# 1.net
KiCad netlist of a schematic drawn in EAGLE
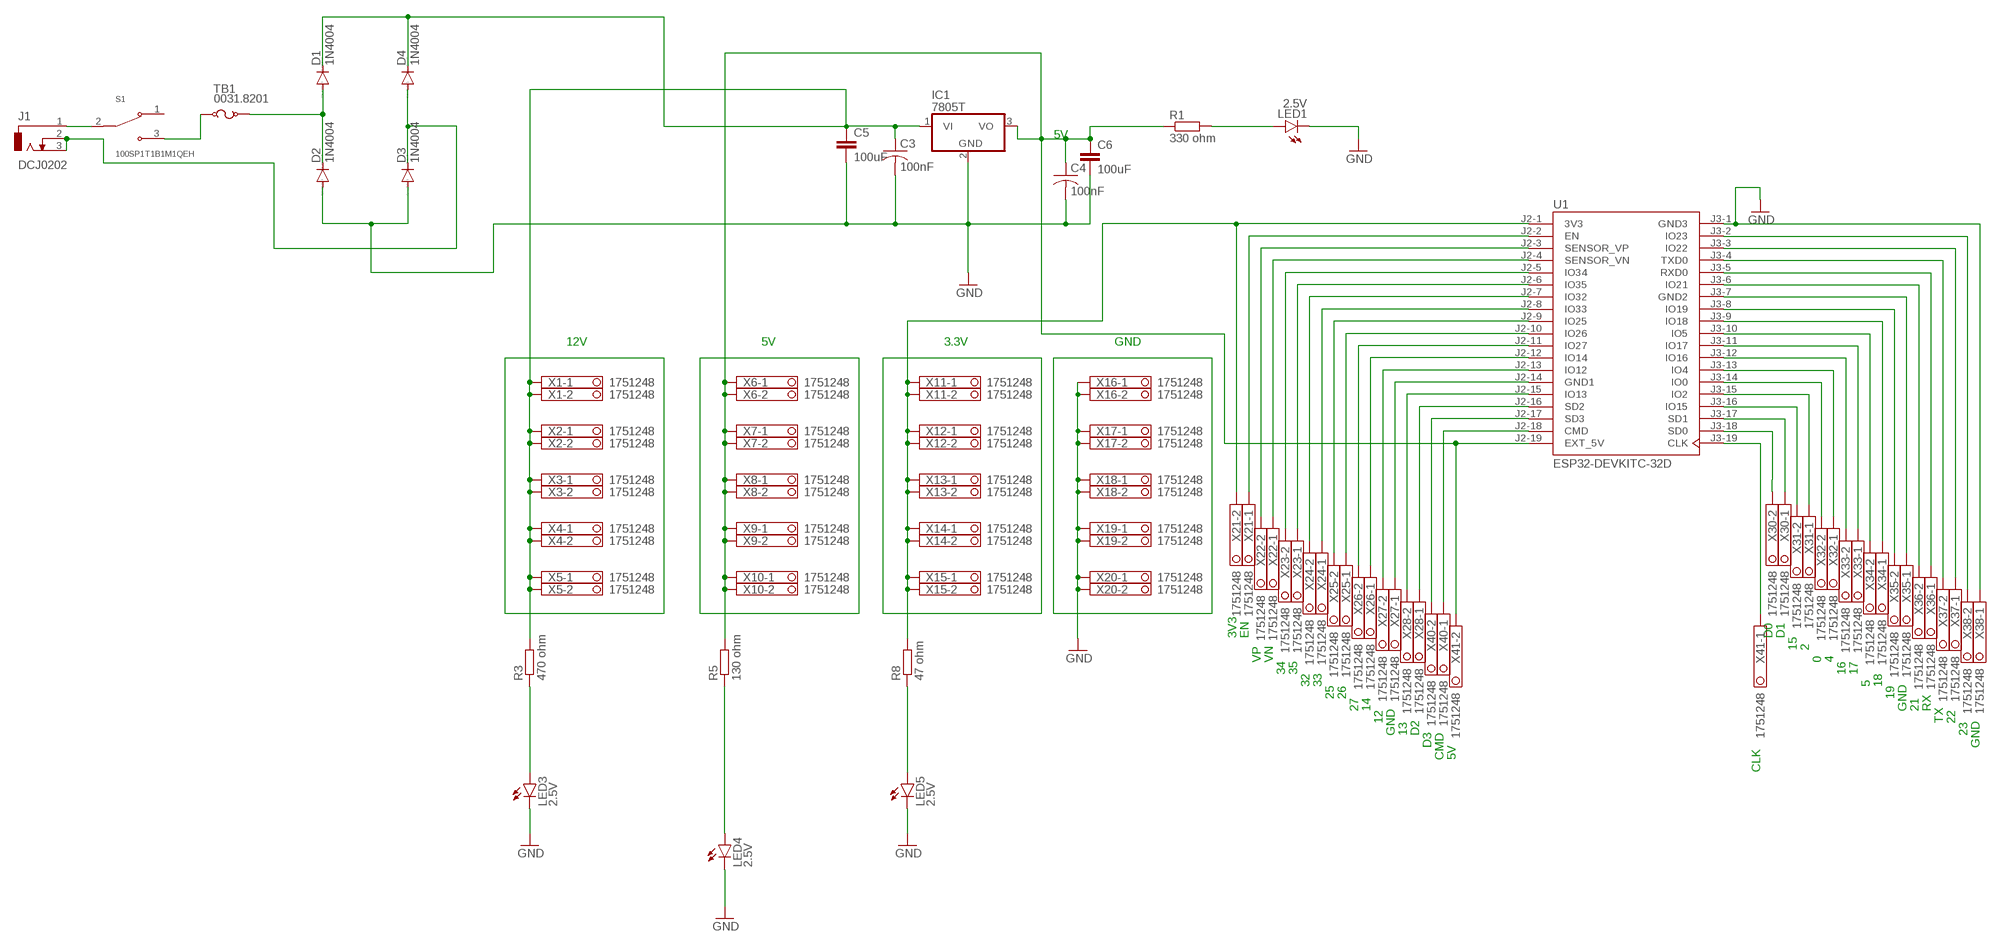
[diagram p0: schematic, sheet 1]

(export (version "E")
  (design (tool "Eeschema 10.0.6"))
  (components
    (comp (ref "C3")
      (value "100nF")
      (footprint "eagle-import:C025-024X044")
      (libsource (lib "eagle-import") (part "C-US025-024X044"))
    )
    (comp (ref "C4")
      (value "100nF")
      (footprint "eagle-import:C025-024X044")
      (libsource (lib "eagle-import") (part "C-US025-024X044"))
    )
    (comp (ref "C5")
      (value "100uF")
      (footprint "eagle-import:C025-050X050")
      (libsource (lib "eagle-import") (part "C-EU025-050X050"))
    )
    (comp (ref "C6")
      (value "100uF")
      (footprint "eagle-import:C025-050X050")
      (libsource (lib "eagle-import") (part "C-EU025-050X050"))
    )
    (comp (ref "D1")
      (value "1N4004")
      (footprint "eagle-import:DO41-10")
      (libsource (lib "eagle-import") (part "1N4004"))
    )
    (comp (ref "D2")
      (value "1N4004")
      (footprint "eagle-import:DO41-10")
      (libsource (lib "eagle-import") (part "1N4004"))
    )
    (comp (ref "D3")
      (value "1N4004")
      (footprint "eagle-import:DO41-10")
      (libsource (lib "eagle-import") (part "1N4004"))
    )
    (comp (ref "D4")
      (value "1N4004")
      (footprint "eagle-import:DO41-10")
      (libsource (lib "eagle-import") (part "1N4004"))
    )
    (comp (ref "IC1")
      (value "7805T")
      (footprint "eagle-import:TO220H")
      (libsource (lib "eagle-import") (part "78T05"))
    )
    (comp (ref "J1")
      (value "DCJ0202")
      (footprint "eagle-import:DCJ0202")
      (libsource (lib "eagle-import") (part "DCJ0202"))
    )
    (comp (ref "LED1")
      (value "2.5V")
      (footprint "eagle-import:LED3MM")
      (libsource (lib "eagle-import") (part "LED3MM"))
    )
    (comp (ref "LED3")
      (value "2.5V")
      (footprint "eagle-import:LED3MM")
      (libsource (lib "eagle-import") (part "LED3MM"))
    )
    (comp (ref "LED4")
      (value "2.5V")
      (footprint "eagle-import:LED3MM")
      (libsource (lib "eagle-import") (part "LED3MM"))
    )
    (comp (ref "LED5")
      (value "2.5V")
      (footprint "eagle-import:LED3MM")
      (libsource (lib "eagle-import") (part "LED3MM"))
    )
    (comp (ref "R1")
      (value "330 ohm")
      (footprint "eagle-import:0207_10")
      (libsource (lib "eagle-import") (part "R-EU_0207/10"))
    )
    (comp (ref "R3")
      (value "470 ohm")
      (footprint "eagle-import:0207_10")
      (libsource (lib "eagle-import") (part "R-EU_0207/10"))
    )
    (comp (ref "R5")
      (value "130 ohm")
      (footprint "eagle-import:0207_10")
      (libsource (lib "eagle-import") (part "R-EU_0207/10"))
    )
    (comp (ref "R8")
      (value "47 ohm")
      (footprint "eagle-import:0207_10")
      (libsource (lib "eagle-import") (part "R-EU_0207/10"))
    )
    (comp (ref "S1")
      (value "100SP1T1B1M1QEH")
      (footprint "eagle-import:SW_100SP1T1B1M1QEH")
      (fields (field (name "MF") "E-Switch"))
      (libsource (lib "eagle-import") (part "100SP1T1B1M1QEH"))
    )
    (comp (ref "TB1")
      (value "0031.8201")
      (footprint "eagle-import:SCHURTER_0031.8201")
      (fields (field (name "MF") "Schurter Inc."))
      (libsource (lib "eagle-import") (part "0031.8201"))
    )
    (comp (ref "U1")
      (value "ESP32-DEVKITC-32D")
      (footprint "eagle-import:MODULE_ESP32-DEVKITC-32D")
      (fields (field (name "MF") "Espressif Systems"))
      (libsource (lib "eagle-import") (part "ESP32-DEVKITC-32D"))
    )
    (comp (ref "X1")
      (value "1751248")
      (footprint "eagle-import:1751248")
      (libsource (lib "eagle-import") (part "1751248"))
    )
    (comp (ref "X2")
      (value "1751248")
      (footprint "eagle-import:1751248")
      (libsource (lib "eagle-import") (part "1751248"))
    )
    (comp (ref "X3")
      (value "1751248")
      (footprint "eagle-import:1751248")
      (libsource (lib "eagle-import") (part "1751248"))
    )
    (comp (ref "X4")
      (value "1751248")
      (footprint "eagle-import:1751248")
      (libsource (lib "eagle-import") (part "1751248"))
    )
    (comp (ref "X5")
      (value "1751248")
      (footprint "eagle-import:1751248")
      (libsource (lib "eagle-import") (part "1751248"))
    )
    (comp (ref "X6")
      (value "1751248")
      (footprint "eagle-import:1751248")
      (libsource (lib "eagle-import") (part "1751248"))
    )
    (comp (ref "X7")
      (value "1751248")
      (footprint "eagle-import:1751248")
      (libsource (lib "eagle-import") (part "1751248"))
    )
    (comp (ref "X8")
      (value "1751248")
      (footprint "eagle-import:1751248")
      (libsource (lib "eagle-import") (part "1751248"))
    )
    (comp (ref "X9")
      (value "1751248")
      (footprint "eagle-import:1751248")
      (libsource (lib "eagle-import") (part "1751248"))
    )
    (comp (ref "X10")
      (value "1751248")
      (footprint "eagle-import:1751248")
      (libsource (lib "eagle-import") (part "1751248"))
    )
    (comp (ref "X11")
      (value "1751248")
      (footprint "eagle-import:1751248")
      (libsource (lib "eagle-import") (part "1751248"))
    )
    (comp (ref "X12")
      (value "1751248")
      (footprint "eagle-import:1751248")
      (libsource (lib "eagle-import") (part "1751248"))
    )
    (comp (ref "X13")
      (value "1751248")
      (footprint "eagle-import:1751248")
      (libsource (lib "eagle-import") (part "1751248"))
    )
    (comp (ref "X14")
      (value "1751248")
      (footprint "eagle-import:1751248")
      (libsource (lib "eagle-import") (part "1751248"))
    )
    (comp (ref "X15")
      (value "1751248")
      (footprint "eagle-import:1751248")
      (libsource (lib "eagle-import") (part "1751248"))
    )
    (comp (ref "X16")
      (value "1751248")
      (footprint "eagle-import:1751248")
      (libsource (lib "eagle-import") (part "1751248"))
    )
    (comp (ref "X17")
      (value "1751248")
      (footprint "eagle-import:1751248")
      (libsource (lib "eagle-import") (part "1751248"))
    )
    (comp (ref "X18")
      (value "1751248")
      (footprint "eagle-import:1751248")
      (libsource (lib "eagle-import") (part "1751248"))
    )
    (comp (ref "X19")
      (value "1751248")
      (footprint "eagle-import:1751248")
      (libsource (lib "eagle-import") (part "1751248"))
    )
    (comp (ref "X20")
      (value "1751248")
      (footprint "eagle-import:1751248")
      (libsource (lib "eagle-import") (part "1751248"))
    )
    (comp (ref "X21")
      (value "1751248")
      (footprint "eagle-import:1751248")
      (libsource (lib "eagle-import") (part "1751248"))
    )
    (comp (ref "X22")
      (value "1751248")
      (footprint "eagle-import:1751248")
      (libsource (lib "eagle-import") (part "1751248"))
    )
    (comp (ref "X23")
      (value "1751248")
      (footprint "eagle-import:1751248")
      (libsource (lib "eagle-import") (part "1751248"))
    )
    (comp (ref "X24")
      (value "1751248")
      (footprint "eagle-import:1751248")
      (libsource (lib "eagle-import") (part "1751248"))
    )
    (comp (ref "X25")
      (value "1751248")
      (footprint "eagle-import:1751248")
      (libsource (lib "eagle-import") (part "1751248"))
    )
    (comp (ref "X26")
      (value "1751248")
      (footprint "eagle-import:1751248")
      (libsource (lib "eagle-import") (part "1751248"))
    )
    (comp (ref "X27")
      (value "1751248")
      (footprint "eagle-import:1751248")
      (libsource (lib "eagle-import") (part "1751248"))
    )
    (comp (ref "X28")
      (value "1751248")
      (footprint "eagle-import:1751248")
      (libsource (lib "eagle-import") (part "1751248"))
    )
    (comp (ref "X30")
      (value "1751248")
      (footprint "eagle-import:1751248")
      (libsource (lib "eagle-import") (part "1751248"))
    )
    (comp (ref "X31")
      (value "1751248")
      (footprint "eagle-import:1751248")
      (libsource (lib "eagle-import") (part "1751248"))
    )
    (comp (ref "X32")
      (value "1751248")
      (footprint "eagle-import:1751248")
      (libsource (lib "eagle-import") (part "1751248"))
    )
    (comp (ref "X33")
      (value "1751248")
      (footprint "eagle-import:1751248")
      (libsource (lib "eagle-import") (part "1751248"))
    )
    (comp (ref "X34")
      (value "1751248")
      (footprint "eagle-import:1751248")
      (libsource (lib "eagle-import") (part "1751248"))
    )
    (comp (ref "X35")
      (value "1751248")
      (footprint "eagle-import:1751248")
      (libsource (lib "eagle-import") (part "1751248"))
    )
    (comp (ref "X36")
      (value "1751248")
      (footprint "eagle-import:1751248")
      (libsource (lib "eagle-import") (part "1751248"))
    )
    (comp (ref "X37")
      (value "1751248")
      (footprint "eagle-import:1751248")
      (libsource (lib "eagle-import") (part "1751248"))
    )
    (comp (ref "X38")
      (value "1751248")
      (footprint "eagle-import:1751248")
      (libsource (lib "eagle-import") (part "1751248"))
    )
    (comp (ref "X40")
      (value "1751248")
      (footprint "eagle-import:1751248")
      (libsource (lib "eagle-import") (part "1751248"))
    )
    (comp (ref "X41")
      (value "1751248")
      (footprint "eagle-import:1751248")
      (libsource (lib "eagle-import") (part "1751248"))
    )
  )
  (nets
    (net (code "1") (name "GND") (class "Default")
      (node (ref "C3") (pin "2") (pinfunction "2_2") (pintype "passive"))
      (node (ref "C4") (pin "2") (pinfunction "2_2") (pintype "passive"))
      (node (ref "C5") (pin "2") (pinfunction "2_2") (pintype "passive"))
      (node (ref "C6") (pin "2") (pinfunction "2_2") (pintype "passive"))
      (node (ref "D2") (pin "A") (pinfunction "A_A") (pintype "passive"))
      (node (ref "D3") (pin "A") (pinfunction "A_A") (pintype "passive"))
      (node (ref "IC1") (pin "2") (pinfunction "GND_2") (pintype "passive"))
      (node (ref "LED1") (pin "K") (pinfunction "C_K") (pintype "passive"))
      (node (ref "LED3") (pin "K") (pinfunction "C_K") (pintype "passive"))
      (node (ref "LED4") (pin "K") (pinfunction "C_K") (pintype "passive"))
      (node (ref "LED5") (pin "K") (pinfunction "C_K") (pintype "passive"))
      (node (ref "U1") (pin "J3-1") (pinfunction "GND3_J3-1") (pintype "power_in"))
      (node (ref "X16") (pin "1") (pinfunction "K_1") (pintype "passive"))
      (node (ref "X16") (pin "2") (pinfunction "K_2") (pintype "passive"))
      (node (ref "X17") (pin "1") (pinfunction "K_1") (pintype "passive"))
      (node (ref "X17") (pin "2") (pinfunction "K_2") (pintype "passive"))
      (node (ref "X18") (pin "1") (pinfunction "K_1") (pintype "passive"))
      (node (ref "X18") (pin "2") (pinfunction "K_2") (pintype "passive"))
      (node (ref "X19") (pin "1") (pinfunction "K_1") (pintype "passive"))
      (node (ref "X19") (pin "2") (pinfunction "K_2") (pintype "passive"))
      (node (ref "X20") (pin "1") (pinfunction "K_1") (pintype "passive"))
      (node (ref "X20") (pin "2") (pinfunction "K_2") (pintype "passive"))
      (node (ref "X38") (pin "1") (pinfunction "K_1") (pintype "passive"))
    )
    (net (code "2") (name "Net-(D1-PadA)") (class "Default")
      (node (ref "D1") (pin "A") (pinfunction "A_A") (pintype "passive"))
      (node (ref "D2") (pin "C") (pinfunction "C_C") (pintype "passive"))
      (node (ref "TB1") (pin "2") (pinfunction "2_2") (pintype "passive"))
    )
    (net (code "3") (name "Net-(D3-PadC)") (class "Default")
      (node (ref "D3") (pin "C") (pinfunction "C_C") (pintype "passive"))
      (node (ref "D4") (pin "A") (pinfunction "A_A") (pintype "passive"))
      (node (ref "J1") (pin "2") (pinfunction "2_2") (pintype "passive"))
      (node (ref "J1") (pin "3") (pinfunction "3_3") (pintype "passive"))
    )
    (net (code "4") (name "Net-(IC1-VI)") (class "Default")
      (node (ref "C3") (pin "1") (pinfunction "1_1") (pintype "passive"))
      (node (ref "C5") (pin "1") (pinfunction "1_1") (pintype "passive"))
      (node (ref "D1") (pin "C") (pinfunction "C_C") (pintype "passive"))
      (node (ref "D4") (pin "C") (pinfunction "C_C") (pintype "passive"))
      (node (ref "IC1") (pin "1") (pinfunction "VI_1") (pintype "input"))
      (node (ref "R3") (pin "2") (pinfunction "2_2") (pintype "passive"))
      (node (ref "X1") (pin "1") (pinfunction "K_1") (pintype "passive"))
      (node (ref "X1") (pin "2") (pinfunction "K_2") (pintype "passive"))
      (node (ref "X2") (pin "1") (pinfunction "K_1") (pintype "passive"))
      (node (ref "X2") (pin "2") (pinfunction "K_2") (pintype "passive"))
      (node (ref "X3") (pin "1") (pinfunction "K_1") (pintype "passive"))
      (node (ref "X3") (pin "2") (pinfunction "K_2") (pintype "passive"))
      (node (ref "X4") (pin "1") (pinfunction "K_1") (pintype "passive"))
      (node (ref "X4") (pin "2") (pinfunction "K_2") (pintype "passive"))
      (node (ref "X5") (pin "1") (pinfunction "K_1") (pintype "passive"))
      (node (ref "X5") (pin "2") (pinfunction "K_2") (pintype "passive"))
    )
    (net (code "5") (name "Net-(IC1-VO)") (class "Default")
      (node (ref "C4") (pin "1") (pinfunction "1_1") (pintype "passive"))
      (node (ref "C6") (pin "1") (pinfunction "1_1") (pintype "passive"))
      (node (ref "IC1") (pin "3") (pinfunction "VO_3") (pintype "passive"))
      (node (ref "R1") (pin "1") (pinfunction "1_1") (pintype "passive"))
      (node (ref "R5") (pin "2") (pinfunction "2_2") (pintype "passive"))
      (node (ref "U1") (pin "J2-19") (pinfunction "EXT_5V_J2-19") (pintype "power_in"))
      (node (ref "X10") (pin "1") (pinfunction "K_1") (pintype "passive"))
      (node (ref "X10") (pin "2") (pinfunction "K_2") (pintype "passive"))
      (node (ref "X41") (pin "2") (pinfunction "K_2") (pintype "passive"))
      (node (ref "X6") (pin "1") (pinfunction "K_1") (pintype "passive"))
      (node (ref "X6") (pin "2") (pinfunction "K_2") (pintype "passive"))
      (node (ref "X7") (pin "1") (pinfunction "K_1") (pintype "passive"))
      (node (ref "X7") (pin "2") (pinfunction "K_2") (pintype "passive"))
      (node (ref "X8") (pin "1") (pinfunction "K_1") (pintype "passive"))
      (node (ref "X8") (pin "2") (pinfunction "K_2") (pintype "passive"))
      (node (ref "X9") (pin "1") (pinfunction "K_1") (pintype "passive"))
      (node (ref "X9") (pin "2") (pinfunction "K_2") (pintype "passive"))
    )
    (net (code "6") (name "Net-(J1-Pad1)") (class "Default")
      (node (ref "J1") (pin "1") (pinfunction "1_1") (pintype "passive"))
      (node (ref "S1") (pin "2") (pinfunction "2_2") (pintype "passive"))
    )
    (net (code "7") (name "Net-(LED1-PadA)") (class "Default")
      (node (ref "LED1") (pin "A") (pinfunction "A_A") (pintype "passive"))
      (node (ref "R1") (pin "2") (pinfunction "2_2") (pintype "passive"))
    )
    (net (code "8") (name "Net-(LED3-PadA)") (class "Default")
      (node (ref "LED3") (pin "A") (pinfunction "A_A") (pintype "passive"))
      (node (ref "R3") (pin "1") (pinfunction "1_1") (pintype "passive"))
    )
    (net (code "9") (name "Net-(LED4-PadA)") (class "Default")
      (node (ref "LED4") (pin "A") (pinfunction "A_A") (pintype "passive"))
      (node (ref "R5") (pin "1") (pinfunction "1_1") (pintype "passive"))
    )
    (net (code "10") (name "Net-(LED5-PadA)") (class "Default")
      (node (ref "LED5") (pin "A") (pinfunction "A_A") (pintype "passive"))
      (node (ref "R8") (pin "1") (pinfunction "1_1") (pintype "passive"))
    )
    (net (code "11") (name "Net-(S1-Pad3)") (class "Default")
      (node (ref "S1") (pin "3") (pinfunction "3_3") (pintype "passive"))
      (node (ref "TB1") (pin "1") (pinfunction "1_1") (pintype "passive"))
    )
    (net (code "12") (name "Net-(U1-3V3)") (class "Default")
      (node (ref "R8") (pin "2") (pinfunction "2_2") (pintype "passive"))
      (node (ref "U1") (pin "J2-1") (pinfunction "3V3_J2-1") (pintype "power_in"))
      (node (ref "X11") (pin "1") (pinfunction "K_1") (pintype "passive"))
      (node (ref "X11") (pin "2") (pinfunction "K_2") (pintype "passive"))
      (node (ref "X12") (pin "1") (pinfunction "K_1") (pintype "passive"))
      (node (ref "X12") (pin "2") (pinfunction "K_2") (pintype "passive"))
      (node (ref "X13") (pin "1") (pinfunction "K_1") (pintype "passive"))
      (node (ref "X13") (pin "2") (pinfunction "K_2") (pintype "passive"))
      (node (ref "X14") (pin "1") (pinfunction "K_1") (pintype "passive"))
      (node (ref "X14") (pin "2") (pinfunction "K_2") (pintype "passive"))
      (node (ref "X15") (pin "1") (pinfunction "K_1") (pintype "passive"))
      (node (ref "X15") (pin "2") (pinfunction "K_2") (pintype "passive"))
      (node (ref "X21") (pin "2") (pinfunction "K_2") (pintype "passive"))
    )
    (net (code "13") (name "Net-(U1-CLK)") (class "Default")
      (node (ref "U1") (pin "J3-19") (pinfunction "CLK_J3-19") (pintype "input"))
      (node (ref "X41") (pin "1") (pinfunction "K_1") (pintype "passive"))
    )
    (net (code "14") (name "Net-(U1-CMD)") (class "Default")
      (node (ref "U1") (pin "J2-18") (pinfunction "CMD_J2-18") (pintype "bidirectional"))
      (node (ref "X40") (pin "1") (pinfunction "K_1") (pintype "passive"))
    )
    (net (code "15") (name "Net-(U1-EN)") (class "Default")
      (node (ref "U1") (pin "J2-2") (pinfunction "EN_J2-2") (pintype "input"))
      (node (ref "X21") (pin "1") (pinfunction "K_1") (pintype "passive"))
    )
    (net (code "16") (name "Net-(U1-GND1)") (class "Default")
      (node (ref "U1") (pin "J2-14") (pinfunction "GND1_J2-14") (pintype "power_in"))
      (node (ref "X27") (pin "1") (pinfunction "K_1") (pintype "passive"))
    )
    (net (code "17") (name "Net-(U1-GND2)") (class "Default")
      (node (ref "U1") (pin "J3-7") (pinfunction "GND2_J3-7") (pintype "power_in"))
      (node (ref "X35") (pin "1") (pinfunction "K_1") (pintype "passive"))
    )
    (net (code "18") (name "Net-(U1-IO0)") (class "Default")
      (node (ref "U1") (pin "J3-14") (pinfunction "IO0_J3-14") (pintype "bidirectional"))
      (node (ref "X32") (pin "2") (pinfunction "K_2") (pintype "passive"))
    )
    (net (code "19") (name "Net-(U1-IO2)") (class "Default")
      (node (ref "U1") (pin "J3-15") (pinfunction "IO2_J3-15") (pintype "bidirectional"))
      (node (ref "X31") (pin "1") (pinfunction "K_1") (pintype "passive"))
    )
    (net (code "20") (name "Net-(U1-IO4)") (class "Default")
      (node (ref "U1") (pin "J3-13") (pinfunction "IO4_J3-13") (pintype "bidirectional"))
      (node (ref "X32") (pin "1") (pinfunction "K_1") (pintype "passive"))
    )
    (net (code "21") (name "Net-(U1-IO5)") (class "Default")
      (node (ref "U1") (pin "J3-10") (pinfunction "IO5_J3-10") (pintype "bidirectional"))
      (node (ref "X34") (pin "2") (pinfunction "K_2") (pintype "passive"))
    )
    (net (code "22") (name "Net-(U1-IO12)") (class "Default")
      (node (ref "U1") (pin "J2-13") (pinfunction "IO12_J2-13") (pintype "bidirectional"))
      (node (ref "X27") (pin "2") (pinfunction "K_2") (pintype "passive"))
    )
    (net (code "23") (name "Net-(U1-IO13)") (class "Default")
      (node (ref "U1") (pin "J2-15") (pinfunction "IO13_J2-15") (pintype "bidirectional"))
      (node (ref "X28") (pin "2") (pinfunction "K_2") (pintype "passive"))
    )
    (net (code "24") (name "Net-(U1-IO14)") (class "Default")
      (node (ref "U1") (pin "J2-12") (pinfunction "IO14_J2-12") (pintype "bidirectional"))
      (node (ref "X26") (pin "1") (pinfunction "K_1") (pintype "passive"))
    )
    (net (code "25") (name "Net-(U1-IO15)") (class "Default")
      (node (ref "U1") (pin "J3-16") (pinfunction "IO15_J3-16") (pintype "bidirectional"))
      (node (ref "X31") (pin "2") (pinfunction "K_2") (pintype "passive"))
    )
    (net (code "26") (name "Net-(U1-IO16)") (class "Default")
      (node (ref "U1") (pin "J3-12") (pinfunction "IO16_J3-12") (pintype "bidirectional"))
      (node (ref "X33") (pin "2") (pinfunction "K_2") (pintype "passive"))
    )
    (net (code "27") (name "Net-(U1-IO17)") (class "Default")
      (node (ref "U1") (pin "J3-11") (pinfunction "IO17_J3-11") (pintype "bidirectional"))
      (node (ref "X33") (pin "1") (pinfunction "K_1") (pintype "passive"))
    )
    (net (code "28") (name "Net-(U1-IO18)") (class "Default")
      (node (ref "U1") (pin "J3-9") (pinfunction "IO18_J3-9") (pintype "bidirectional"))
      (node (ref "X34") (pin "1") (pinfunction "K_1") (pintype "passive"))
    )
    (net (code "29") (name "Net-(U1-IO19)") (class "Default")
      (node (ref "U1") (pin "J3-8") (pinfunction "IO19_J3-8") (pintype "bidirectional"))
      (node (ref "X35") (pin "2") (pinfunction "K_2") (pintype "passive"))
    )
    (net (code "30") (name "Net-(U1-IO21)") (class "Default")
      (node (ref "U1") (pin "J3-6") (pinfunction "IO21_J3-6") (pintype "bidirectional"))
      (node (ref "X36") (pin "2") (pinfunction "K_2") (pintype "passive"))
    )
    (net (code "31") (name "Net-(U1-IO22)") (class "Default")
      (node (ref "U1") (pin "J3-3") (pinfunction "IO22_J3-3") (pintype "bidirectional"))
      (node (ref "X37") (pin "1") (pinfunction "K_1") (pintype "passive"))
    )
    (net (code "32") (name "Net-(U1-IO23)") (class "Default")
      (node (ref "U1") (pin "J3-2") (pinfunction "IO23_J3-2") (pintype "bidirectional"))
      (node (ref "X38") (pin "2") (pinfunction "K_2") (pintype "passive"))
    )
    (net (code "33") (name "Net-(U1-IO25)") (class "Default")
      (node (ref "U1") (pin "J2-9") (pinfunction "IO25_J2-9") (pintype "bidirectional"))
      (node (ref "X25") (pin "2") (pinfunction "K_2") (pintype "passive"))
    )
    (net (code "34") (name "Net-(U1-IO26)") (class "Default")
      (node (ref "U1") (pin "J2-10") (pinfunction "IO26_J2-10") (pintype "bidirectional"))
      (node (ref "X25") (pin "1") (pinfunction "K_1") (pintype "passive"))
    )
    (net (code "35") (name "Net-(U1-IO27)") (class "Default")
      (node (ref "U1") (pin "J2-11") (pinfunction "IO27_J2-11") (pintype "bidirectional"))
      (node (ref "X26") (pin "2") (pinfunction "K_2") (pintype "passive"))
    )
    (net (code "36") (name "Net-(U1-IO32)") (class "Default")
      (node (ref "U1") (pin "J2-7") (pinfunction "IO32_J2-7") (pintype "bidirectional"))
      (node (ref "X24") (pin "2") (pinfunction "K_2") (pintype "passive"))
    )
    (net (code "37") (name "Net-(U1-IO33)") (class "Default")
      (node (ref "U1") (pin "J2-8") (pinfunction "IO33_J2-8") (pintype "bidirectional"))
      (node (ref "X24") (pin "1") (pinfunction "K_1") (pintype "passive"))
    )
    (net (code "38") (name "Net-(U1-IO34)") (class "Default")
      (node (ref "U1") (pin "J2-5") (pinfunction "IO34_J2-5") (pintype "bidirectional"))
      (node (ref "X23") (pin "2") (pinfunction "K_2") (pintype "passive"))
    )
    (net (code "39") (name "Net-(U1-IO35)") (class "Default")
      (node (ref "U1") (pin "J2-6") (pinfunction "IO35_J2-6") (pintype "bidirectional"))
      (node (ref "X23") (pin "1") (pinfunction "K_1") (pintype "passive"))
    )
    (net (code "40") (name "Net-(U1-RXD0)") (class "Default")
      (node (ref "U1") (pin "J3-5") (pinfunction "RXD0_J3-5") (pintype "input"))
      (node (ref "X36") (pin "1") (pinfunction "K_1") (pintype "passive"))
    )
    (net (code "41") (name "Net-(U1-SD0)") (class "Default")
      (node (ref "U1") (pin "J3-18") (pinfunction "SD0_J3-18") (pintype "bidirectional"))
      (node (ref "X30") (pin "2") (pinfunction "K_2") (pintype "passive"))
    )
    (net (code "42") (name "Net-(U1-SD1)") (class "Default")
      (node (ref "U1") (pin "J3-17") (pinfunction "SD1_J3-17") (pintype "bidirectional"))
      (node (ref "X30") (pin "1") (pinfunction "K_1") (pintype "passive"))
    )
    (net (code "43") (name "Net-(U1-SD2)") (class "Default")
      (node (ref "U1") (pin "J2-16") (pinfunction "SD2_J2-16") (pintype "bidirectional"))
      (node (ref "X28") (pin "1") (pinfunction "K_1") (pintype "passive"))
    )
    (net (code "44") (name "Net-(U1-SD3)") (class "Default")
      (node (ref "U1") (pin "J2-17") (pinfunction "SD3_J2-17") (pintype "bidirectional"))
      (node (ref "X40") (pin "2") (pinfunction "K_2") (pintype "passive"))
    )
    (net (code "45") (name "Net-(U1-SENSOR_VN)") (class "Default")
      (node (ref "U1") (pin "J2-4") (pinfunction "SENSOR_VN_J2-4") (pintype "input"))
      (node (ref "X22") (pin "1") (pinfunction "K_1") (pintype "passive"))
    )
    (net (code "46") (name "Net-(U1-SENSOR_VP)") (class "Default")
      (node (ref "U1") (pin "J2-3") (pinfunction "SENSOR_VP_J2-3") (pintype "input"))
      (node (ref "X22") (pin "2") (pinfunction "K_2") (pintype "passive"))
    )
    (net (code "47") (name "Net-(U1-TXD0)") (class "Default")
      (node (ref "U1") (pin "J3-4") (pinfunction "TXD0_J3-4") (pintype "output"))
      (node (ref "X37") (pin "2") (pinfunction "K_2") (pintype "passive"))
    )
    (net (code "48") (name "unconnected-(S1-Pad1)") (class "Default")
      (node (ref "S1") (pin "1") (pinfunction "1_1") (pintype "passive"))
    )
  )
)
